# STM32.net
KiCad netlist of a schematic drawn in Altium Designer
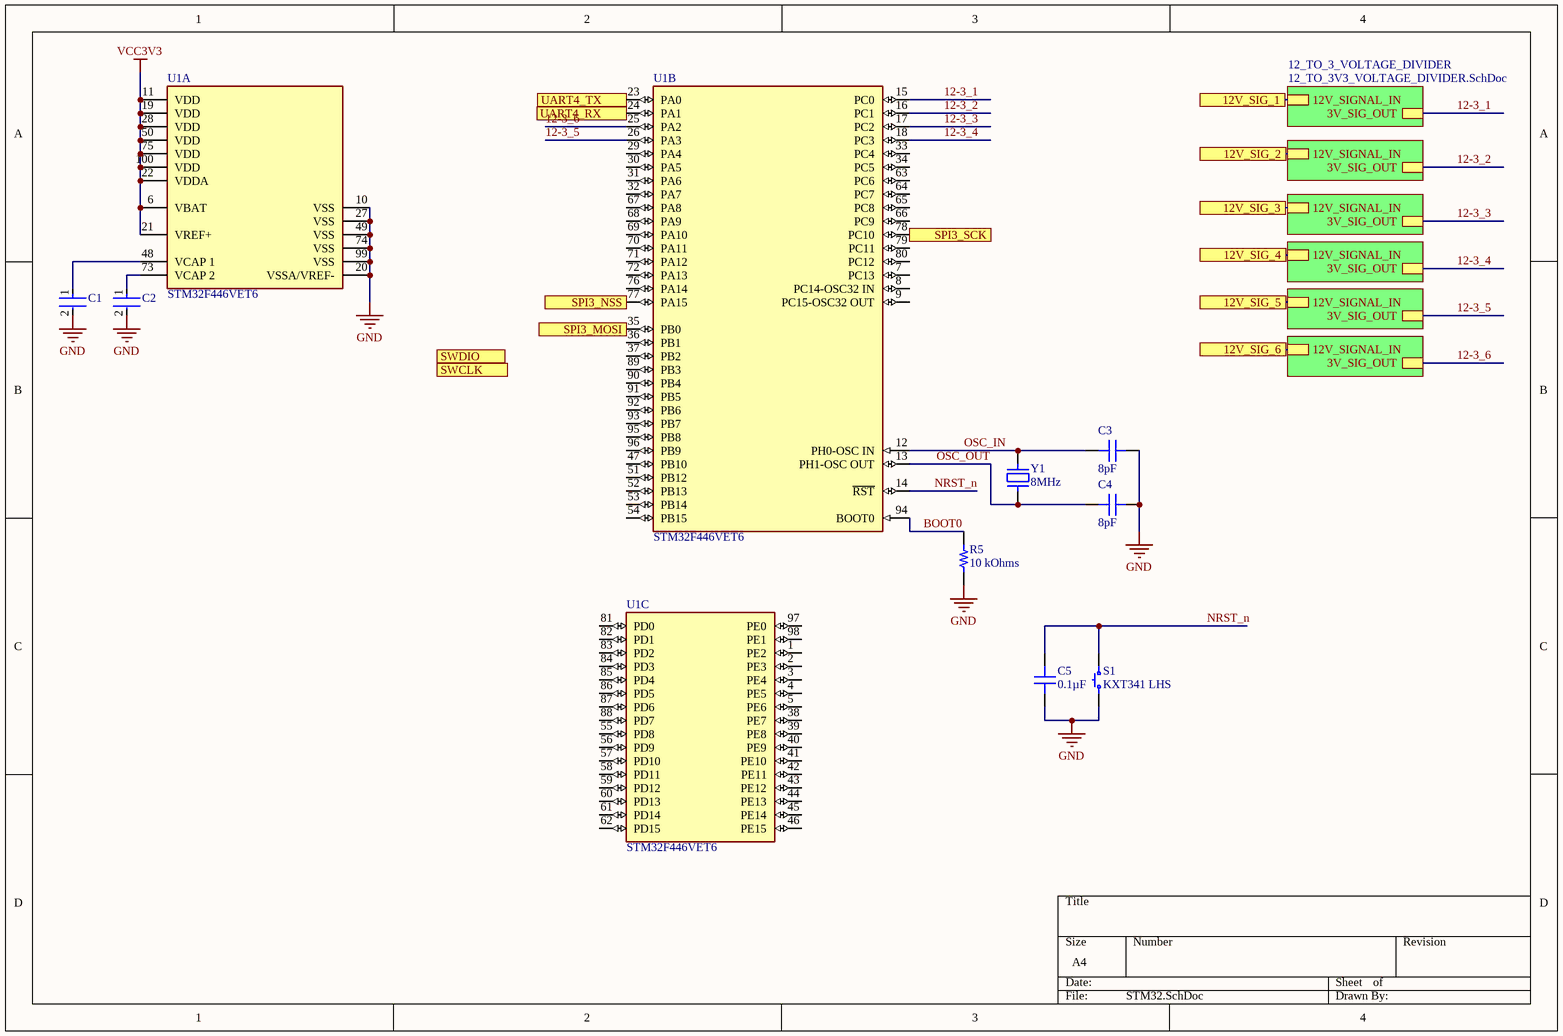
[diagram p0: STM32.SchDoc]

(export (version "E")
  (design (tool "Eeschema 10.0.6"))
  (components
    (comp (ref "C1")
      (value "GRM188R71A225KE15D")
      (footprint "FP-GRM188-0_1-e0_2_0_5-MFG")
      (description "Chip Multilayer Ceramic Capacitors for General Purpose, 0603, 2.2uF, X7R, 15%, 10%, 10V")
      (fields (field (name "VOLTAGE") "10V") (field (name "TOLERANCE") "10%"))
      (libsource (lib "Altium Content Vault") (part "11868f565c42a9108669ba33697ecf6"))
    )
    (comp (ref "C2")
      (value "GRM188R71A225KE15D")
      (footprint "FP-GRM188-0_1-e0_2_0_5-MFG")
      (description "Chip Multilayer Ceramic Capacitors for General Purpose, 0603, 2.2uF, X7R, 15%, 10%, 10V")
      (fields (field (name "VOLTAGE") "10V") (field (name "TOLERANCE") "10%"))
      (libsource (lib "Altium Content Vault") (part "11868f565c42a9108669ba33697ecf6"))
    )
    (comp (ref "C3")
      (value "8pF")
      (footprint "CAP 0402_1005")
      (description "CAP CER 8PF 50V NP0 0402")
      (fields
        (field (name "PART NUMBER") "C1005NP01H080D050BA")
        (field (name "MANUFACTURER") "TDK Corporation")
      )
      (libsource (lib "Celestial") (part "Capacitor"))
    )
    (comp (ref "C4")
      (value "8pF")
      (footprint "CAP 0402_1005")
      (description "CAP CER 8PF 50V NP0 0402")
      (fields
        (field (name "PART NUMBER") "C1005NP01H080D050BA")
        (field (name "MANUFACTURER") "TDK Corporation")
      )
      (libsource (lib "Celestial") (part "Capacitor"))
    )
    (comp (ref "C5")
      (value "0.1µF")
      (footprint "CAP 0402_1005")
      (description "CAP CER 0402 0.1UF 16V X7R 10%")
      (fields (field (name "PART NUMBER") "C0402C104K4RECAUTO") (field (name "MANUFACTURER") "KEMET"))
      (libsource (lib "CAL") (part "Capacitor"))
    )
    (comp (ref "R5")
      (value "10 kOhms")
      (footprint "RES 0402_1005")
      (description "RES SMD 10K OHM 0.5% 1/16W 0402")
      (fields (field (name "PART NUMBER") "CRCW040210K0DHEDP") (field (name "MANUFACTURER") "Vishay Dale"))
      (libsource (lib "CAL") (part "Resistor"))
    )
    (comp (ref "S1")
      (value "KXT341 LHS")
      (footprint "C&K KXT3")
      (description "SWITCH TACTILE SPST-NO 0.02A 15V")
      (fields (field (name "MANUFACTURER") "C&K"))
      (libsource (lib "Celestial") (part "SPST-NO 2 PIN"))
    )
    (comp (ref "U1")
      (value "STM32F446VET6")
      (footprint "FP-LQFP100-1L-MFG")
      (description "IC MCU 32BIT 512KB FLASH 100LQFP")
      (fields
        (field (name "OCTOPART") "https://octopart.com/stm32f446vet6-stmicroelectronics-52642922")
        (field (name "MANUFACTURER") "STMicroelectronics")
      )
      (libsource (lib "Altium Content Vault") (part "8e3e88e6cb74ec1f9e49940598abbc7"))
    )
    (comp (ref "Y1")
      (value "8MHz")
      (footprint "NDK NX3225GD")
      (description "CRYSTAL 8.0000MHZ 8PF SMD")
      (fields
        (field (name "PART NUMBER") "NX3225GD-8MHZ-STD-CRA-3")
        (field (name "MANUFACTURER") "NDK America, Inc.")
      )
      (libsource (lib "Celestial") (part "NDK NX3225GD"))
    )
  )
  (nets
    (net (code "1") (name "/12-3_1") (class "Default")
      (node (ref "U1") (pin "15") (pinfunction "PC0_15") (pintype "bidirectional"))
    )
    (net (code "2") (name "/12-3_2") (class "Default")
      (node (ref "U1") (pin "16") (pinfunction "PC1_16") (pintype "bidirectional"))
    )
    (net (code "3") (name "/12-3_3") (class "Default")
      (node (ref "U1") (pin "17") (pinfunction "PC2_17") (pintype "bidirectional"))
    )
    (net (code "4") (name "/12-3_4") (class "Default")
      (node (ref "U1") (pin "18") (pinfunction "PC3_18") (pintype "bidirectional"))
    )
    (net (code "5") (name "/12-3_5") (class "Default")
      (node (ref "U1") (pin "26") (pinfunction "PA3_26") (pintype "bidirectional"))
    )
    (net (code "6") (name "/12-3_6") (class "Default")
      (node (ref "U1") (pin "25") (pinfunction "PA2_25") (pintype "bidirectional"))
    )
    (net (code "13") (name "/BOOT0") (class "Default")
      (node (ref "R5") (pin "2") (pinfunction "2_2") (pintype "passive"))
      (node (ref "U1") (pin "94") (pinfunction "BOOT0_94") (pintype "input"))
    )
    (net (code "14") (name "/NRST_n") (class "Default")
      (node (ref "C5") (pin "2") (pinfunction "2_2") (pintype "passive"))
      (node (ref "S1") (pin "2") (pinfunction "2_2") (pintype "passive"))
      (node (ref "U1") (pin "14") (pinfunction "~{RST}_14") (pintype "bidirectional"))
    )
    (net (code "15") (name "/OSC_IN") (class "Default")
      (node (ref "C3") (pin "1") (pinfunction "1_1") (pintype "passive"))
      (node (ref "U1") (pin "12") (pinfunction "PH0-OSC_IN_12") (pintype "input"))
      (node (ref "Y1") (pin "2") (pinfunction "2_2") (pintype "passive"))
    )
    (net (code "16") (name "/OSC_OUT") (class "Default")
      (node (ref "C4") (pin "1") (pinfunction "1_1") (pintype "passive"))
      (node (ref "U1") (pin "13") (pinfunction "PH1-OSC_OUT_13") (pintype "bidirectional"))
      (node (ref "Y1") (pin "1") (pinfunction "1_1") (pintype "passive"))
    )
    (net (code "17") (name "/SPI3_MOSI") (class "Default")
      (node (ref "U1") (pin "35") (pinfunction "PB0_35") (pintype "bidirectional"))
    )
    (net (code "18") (name "/SPI3_NSS") (class "Default")
      (node (ref "U1") (pin "77") (pinfunction "PA15_77") (pintype "bidirectional"))
    )
    (net (code "19") (name "/SPI3_SCK") (class "Default")
      (node (ref "U1") (pin "78") (pinfunction "PC10_78") (pintype "bidirectional"))
    )
    (net (code "22") (name "/UART4_RX") (class "Default")
      (node (ref "U1") (pin "24") (pinfunction "PA1_24") (pintype "bidirectional"))
    )
    (net (code "23") (name "/UART4_TX") (class "Default")
      (node (ref "U1") (pin "23") (pinfunction "PA0_23") (pintype "bidirectional"))
    )
    (net (code "24") (name "GND") (class "Default")
      (node (ref "C1") (pin "2") (pinfunction "2_2") (pintype "passive"))
      (node (ref "C2") (pin "2") (pinfunction "2_2") (pintype "passive"))
      (node (ref "C3") (pin "2") (pinfunction "2_2") (pintype "passive"))
      (node (ref "C4") (pin "2") (pinfunction "2_2") (pintype "passive"))
      (node (ref "C5") (pin "1") (pinfunction "1_1") (pintype "passive"))
      (node (ref "R5") (pin "1") (pinfunction "1_1") (pintype "passive"))
      (node (ref "S1") (pin "1") (pinfunction "1_1") (pintype "passive"))
      (node (ref "U1") (pin "10") (pinfunction "VSS_10") (pintype "power_in"))
      (node (ref "U1") (pin "20") (pinfunction "VSSA/VREF-_20") (pintype "power_in"))
      (node (ref "U1") (pin "27") (pinfunction "VSS_27") (pintype "power_in"))
      (node (ref "U1") (pin "49") (pinfunction "VSS_49") (pintype "power_in"))
      (node (ref "U1") (pin "74") (pinfunction "VSS_74") (pintype "power_in"))
      (node (ref "U1") (pin "99") (pinfunction "VSS_99") (pintype "power_in"))
    )
    (net (code "25") (name "Net-(U1A-VCAP_1)") (class "Default")
      (node (ref "C1") (pin "1") (pinfunction "1_1") (pintype "passive"))
      (node (ref "U1") (pin "48") (pinfunction "VCAP_1_48") (pintype "power_in"))
    )
    (net (code "26") (name "Net-(U1A-VCAP_2)") (class "Default")
      (node (ref "C2") (pin "1") (pinfunction "1_1") (pintype "passive"))
      (node (ref "U1") (pin "73") (pinfunction "VCAP_2_73") (pintype "power_in"))
    )
    (net (code "27") (name "VCC3V3") (class "Default")
      (node (ref "U1") (pin "100") (pinfunction "VDD_100") (pintype "power_in"))
      (node (ref "U1") (pin "11") (pinfunction "VDD_11") (pintype "power_in"))
      (node (ref "U1") (pin "19") (pinfunction "VDD_19") (pintype "power_in"))
      (node (ref "U1") (pin "21") (pinfunction "VREF+_21") (pintype "power_in"))
      (node (ref "U1") (pin "22") (pinfunction "VDDA_22") (pintype "power_in"))
      (node (ref "U1") (pin "28") (pinfunction "VDD_28") (pintype "power_in"))
      (node (ref "U1") (pin "50") (pinfunction "VDD_50") (pintype "power_in"))
      (node (ref "U1") (pin "6") (pinfunction "VBAT_6") (pintype "power_in"))
      (node (ref "U1") (pin "75") (pinfunction "VDD_75") (pintype "power_in"))
    )
    (net (code "28") (name "unconnected-(U1B-PA4-Pad29)") (class "Default")
      (node (ref "U1") (pin "29") (pinfunction "PA4_29") (pintype "bidirectional"))
    )
    (net (code "29") (name "unconnected-(U1B-PA5-Pad30)") (class "Default")
      (node (ref "U1") (pin "30") (pinfunction "PA5_30") (pintype "bidirectional"))
    )
    (net (code "30") (name "unconnected-(U1B-PA6-Pad31)") (class "Default")
      (node (ref "U1") (pin "31") (pinfunction "PA6_31") (pintype "bidirectional"))
    )
    (net (code "31") (name "unconnected-(U1B-PA7-Pad32)") (class "Default")
      (node (ref "U1") (pin "32") (pinfunction "PA7_32") (pintype "bidirectional"))
    )
    (net (code "32") (name "unconnected-(U1B-PA8-Pad67)") (class "Default")
      (node (ref "U1") (pin "67") (pinfunction "PA8_67") (pintype "bidirectional"))
    )
    (net (code "33") (name "unconnected-(U1B-PA9-Pad68)") (class "Default")
      (node (ref "U1") (pin "68") (pinfunction "PA9_68") (pintype "bidirectional"))
    )
    (net (code "34") (name "unconnected-(U1B-PA10-Pad69)") (class "Default")
      (node (ref "U1") (pin "69") (pinfunction "PA10_69") (pintype "bidirectional"))
    )
    (net (code "35") (name "unconnected-(U1B-PA11-Pad70)") (class "Default")
      (node (ref "U1") (pin "70") (pinfunction "PA11_70") (pintype "bidirectional"))
    )
    (net (code "36") (name "unconnected-(U1B-PA12-Pad71)") (class "Default")
      (node (ref "U1") (pin "71") (pinfunction "PA12_71") (pintype "bidirectional"))
    )
    (net (code "37") (name "unconnected-(U1B-PA13-Pad72)") (class "Default")
      (node (ref "U1") (pin "72") (pinfunction "PA13_72") (pintype "bidirectional"))
    )
    (net (code "38") (name "unconnected-(U1B-PA14-Pad76)") (class "Default")
      (node (ref "U1") (pin "76") (pinfunction "PA14_76") (pintype "bidirectional"))
    )
    (net (code "39") (name "unconnected-(U1B-PB1-Pad36)") (class "Default")
      (node (ref "U1") (pin "36") (pinfunction "PB1_36") (pintype "bidirectional"))
    )
    (net (code "40") (name "unconnected-(U1B-PB2-Pad37)") (class "Default")
      (node (ref "U1") (pin "37") (pinfunction "PB2_37") (pintype "bidirectional"))
    )
    (net (code "41") (name "unconnected-(U1B-PB3-Pad89)") (class "Default")
      (node (ref "U1") (pin "89") (pinfunction "PB3_89") (pintype "bidirectional"))
    )
    (net (code "42") (name "unconnected-(U1B-PB4-Pad90)") (class "Default")
      (node (ref "U1") (pin "90") (pinfunction "PB4_90") (pintype "bidirectional"))
    )
    (net (code "43") (name "unconnected-(U1B-PB5-Pad91)") (class "Default")
      (node (ref "U1") (pin "91") (pinfunction "PB5_91") (pintype "bidirectional"))
    )
    (net (code "44") (name "unconnected-(U1B-PB6-Pad92)") (class "Default")
      (node (ref "U1") (pin "92") (pinfunction "PB6_92") (pintype "bidirectional"))
    )
    (net (code "45") (name "unconnected-(U1B-PB7-Pad93)") (class "Default")
      (node (ref "U1") (pin "93") (pinfunction "PB7_93") (pintype "bidirectional"))
    )
    (net (code "46") (name "unconnected-(U1B-PB8-Pad95)") (class "Default")
      (node (ref "U1") (pin "95") (pinfunction "PB8_95") (pintype "bidirectional"))
    )
    (net (code "47") (name "unconnected-(U1B-PB9-Pad96)") (class "Default")
      (node (ref "U1") (pin "96") (pinfunction "PB9_96") (pintype "bidirectional"))
    )
    (net (code "48") (name "unconnected-(U1B-PB10-Pad47)") (class "Default")
      (node (ref "U1") (pin "47") (pinfunction "PB10_47") (pintype "bidirectional"))
    )
    (net (code "49") (name "unconnected-(U1B-PB12-Pad51)") (class "Default")
      (node (ref "U1") (pin "51") (pinfunction "PB12_51") (pintype "bidirectional"))
    )
    (net (code "50") (name "unconnected-(U1B-PB13-Pad52)") (class "Default")
      (node (ref "U1") (pin "52") (pinfunction "PB13_52") (pintype "bidirectional"))
    )
    (net (code "51") (name "unconnected-(U1B-PB14-Pad53)") (class "Default")
      (node (ref "U1") (pin "53") (pinfunction "PB14_53") (pintype "bidirectional"))
    )
    (net (code "52") (name "unconnected-(U1B-PB15-Pad54)") (class "Default")
      (node (ref "U1") (pin "54") (pinfunction "PB15_54") (pintype "bidirectional"))
    )
    (net (code "53") (name "unconnected-(U1B-PC4-Pad33)") (class "Default")
      (node (ref "U1") (pin "33") (pinfunction "PC4_33") (pintype "bidirectional"))
    )
    (net (code "54") (name "unconnected-(U1B-PC5-Pad34)") (class "Default")
      (node (ref "U1") (pin "34") (pinfunction "PC5_34") (pintype "bidirectional"))
    )
    (net (code "55") (name "unconnected-(U1B-PC6-Pad63)") (class "Default")
      (node (ref "U1") (pin "63") (pinfunction "PC6_63") (pintype "bidirectional"))
    )
    (net (code "56") (name "unconnected-(U1B-PC7-Pad64)") (class "Default")
      (node (ref "U1") (pin "64") (pinfunction "PC7_64") (pintype "bidirectional"))
    )
    (net (code "57") (name "unconnected-(U1B-PC8-Pad65)") (class "Default")
      (node (ref "U1") (pin "65") (pinfunction "PC8_65") (pintype "bidirectional"))
    )
    (net (code "58") (name "unconnected-(U1B-PC9-Pad66)") (class "Default")
      (node (ref "U1") (pin "66") (pinfunction "PC9_66") (pintype "bidirectional"))
    )
    (net (code "59") (name "unconnected-(U1B-PC11-Pad79)") (class "Default")
      (node (ref "U1") (pin "79") (pinfunction "PC11_79") (pintype "bidirectional"))
    )
    (net (code "60") (name "unconnected-(U1B-PC12-Pad80)") (class "Default")
      (node (ref "U1") (pin "80") (pinfunction "PC12_80") (pintype "bidirectional"))
    )
    (net (code "61") (name "unconnected-(U1B-PC13-Pad7)") (class "Default")
      (node (ref "U1") (pin "7") (pinfunction "PC13_7") (pintype "bidirectional"))
    )
    (net (code "62") (name "unconnected-(U1B-PC14-OSC32_IN-Pad8)") (class "Default")
      (node (ref "U1") (pin "8") (pinfunction "PC14-OSC32_IN_8") (pintype "bidirectional"))
    )
    (net (code "63") (name "unconnected-(U1B-PC15-OSC32_OUT-Pad9)") (class "Default")
      (node (ref "U1") (pin "9") (pinfunction "PC15-OSC32_OUT_9") (pintype "bidirectional"))
    )
    (net (code "64") (name "unconnected-(U1C-PD0-Pad81)") (class "Default")
      (node (ref "U1") (pin "81") (pinfunction "PD0_81") (pintype "bidirectional"))
    )
    (net (code "65") (name "unconnected-(U1C-PD1-Pad82)") (class "Default")
      (node (ref "U1") (pin "82") (pinfunction "PD1_82") (pintype "bidirectional"))
    )
    (net (code "66") (name "unconnected-(U1C-PD2-Pad83)") (class "Default")
      (node (ref "U1") (pin "83") (pinfunction "PD2_83") (pintype "bidirectional"))
    )
    (net (code "67") (name "unconnected-(U1C-PD3-Pad84)") (class "Default")
      (node (ref "U1") (pin "84") (pinfunction "PD3_84") (pintype "bidirectional"))
    )
    (net (code "68") (name "unconnected-(U1C-PD4-Pad85)") (class "Default")
      (node (ref "U1") (pin "85") (pinfunction "PD4_85") (pintype "bidirectional"))
    )
    (net (code "69") (name "unconnected-(U1C-PD5-Pad86)") (class "Default")
      (node (ref "U1") (pin "86") (pinfunction "PD5_86") (pintype "bidirectional"))
    )
    (net (code "70") (name "unconnected-(U1C-PD6-Pad87)") (class "Default")
      (node (ref "U1") (pin "87") (pinfunction "PD6_87") (pintype "bidirectional"))
    )
    (net (code "71") (name "unconnected-(U1C-PD7-Pad88)") (class "Default")
      (node (ref "U1") (pin "88") (pinfunction "PD7_88") (pintype "bidirectional"))
    )
    (net (code "72") (name "unconnected-(U1C-PD8-Pad55)") (class "Default")
      (node (ref "U1") (pin "55") (pinfunction "PD8_55") (pintype "bidirectional"))
    )
    (net (code "73") (name "unconnected-(U1C-PD9-Pad56)") (class "Default")
      (node (ref "U1") (pin "56") (pinfunction "PD9_56") (pintype "bidirectional"))
    )
    (net (code "74") (name "unconnected-(U1C-PD10-Pad57)") (class "Default")
      (node (ref "U1") (pin "57") (pinfunction "PD10_57") (pintype "bidirectional"))
    )
    (net (code "75") (name "unconnected-(U1C-PD11-Pad58)") (class "Default")
      (node (ref "U1") (pin "58") (pinfunction "PD11_58") (pintype "bidirectional"))
    )
    (net (code "76") (name "unconnected-(U1C-PD12-Pad59)") (class "Default")
      (node (ref "U1") (pin "59") (pinfunction "PD12_59") (pintype "bidirectional"))
    )
    (net (code "77") (name "unconnected-(U1C-PD13-Pad60)") (class "Default")
      (node (ref "U1") (pin "60") (pinfunction "PD13_60") (pintype "bidirectional"))
    )
    (net (code "78") (name "unconnected-(U1C-PD14-Pad61)") (class "Default")
      (node (ref "U1") (pin "61") (pinfunction "PD14_61") (pintype "bidirectional"))
    )
    (net (code "79") (name "unconnected-(U1C-PD15-Pad62)") (class "Default")
      (node (ref "U1") (pin "62") (pinfunction "PD15_62") (pintype "bidirectional"))
    )
    (net (code "80") (name "unconnected-(U1C-PE0-Pad97)") (class "Default")
      (node (ref "U1") (pin "97") (pinfunction "PE0_97") (pintype "bidirectional"))
    )
    (net (code "81") (name "unconnected-(U1C-PE1-Pad98)") (class "Default")
      (node (ref "U1") (pin "98") (pinfunction "PE1_98") (pintype "bidirectional"))
    )
    (net (code "82") (name "unconnected-(U1C-PE2-Pad1)") (class "Default")
      (node (ref "U1") (pin "1") (pinfunction "PE2_1") (pintype "bidirectional"))
    )
    (net (code "83") (name "unconnected-(U1C-PE3-Pad2)") (class "Default")
      (node (ref "U1") (pin "2") (pinfunction "PE3_2") (pintype "bidirectional"))
    )
    (net (code "84") (name "unconnected-(U1C-PE4-Pad3)") (class "Default")
      (node (ref "U1") (pin "3") (pinfunction "PE4_3") (pintype "bidirectional"))
    )
    (net (code "85") (name "unconnected-(U1C-PE5-Pad4)") (class "Default")
      (node (ref "U1") (pin "4") (pinfunction "PE5_4") (pintype "bidirectional"))
    )
    (net (code "86") (name "unconnected-(U1C-PE6-Pad5)") (class "Default")
      (node (ref "U1") (pin "5") (pinfunction "PE6_5") (pintype "bidirectional"))
    )
    (net (code "87") (name "unconnected-(U1C-PE7-Pad38)") (class "Default")
      (node (ref "U1") (pin "38") (pinfunction "PE7_38") (pintype "bidirectional"))
    )
    (net (code "88") (name "unconnected-(U1C-PE8-Pad39)") (class "Default")
      (node (ref "U1") (pin "39") (pinfunction "PE8_39") (pintype "bidirectional"))
    )
    (net (code "89") (name "unconnected-(U1C-PE9-Pad40)") (class "Default")
      (node (ref "U1") (pin "40") (pinfunction "PE9_40") (pintype "bidirectional"))
    )
    (net (code "90") (name "unconnected-(U1C-PE10-Pad41)") (class "Default")
      (node (ref "U1") (pin "41") (pinfunction "PE10_41") (pintype "bidirectional"))
    )
    (net (code "91") (name "unconnected-(U1C-PE11-Pad42)") (class "Default")
      (node (ref "U1") (pin "42") (pinfunction "PE11_42") (pintype "bidirectional"))
    )
    (net (code "92") (name "unconnected-(U1C-PE12-Pad43)") (class "Default")
      (node (ref "U1") (pin "43") (pinfunction "PE12_43") (pintype "bidirectional"))
    )
    (net (code "93") (name "unconnected-(U1C-PE13-Pad44)") (class "Default")
      (node (ref "U1") (pin "44") (pinfunction "PE13_44") (pintype "bidirectional"))
    )
    (net (code "94") (name "unconnected-(U1C-PE14-Pad45)") (class "Default")
      (node (ref "U1") (pin "45") (pinfunction "PE14_45") (pintype "bidirectional"))
    )
    (net (code "95") (name "unconnected-(U1C-PE15-Pad46)") (class "Default")
      (node (ref "U1") (pin "46") (pinfunction "PE15_46") (pintype "bidirectional"))
    )
  )
)
